# Artefato4Subtrator.net
KiCad netlist of a schematic drawn in EasyEDA
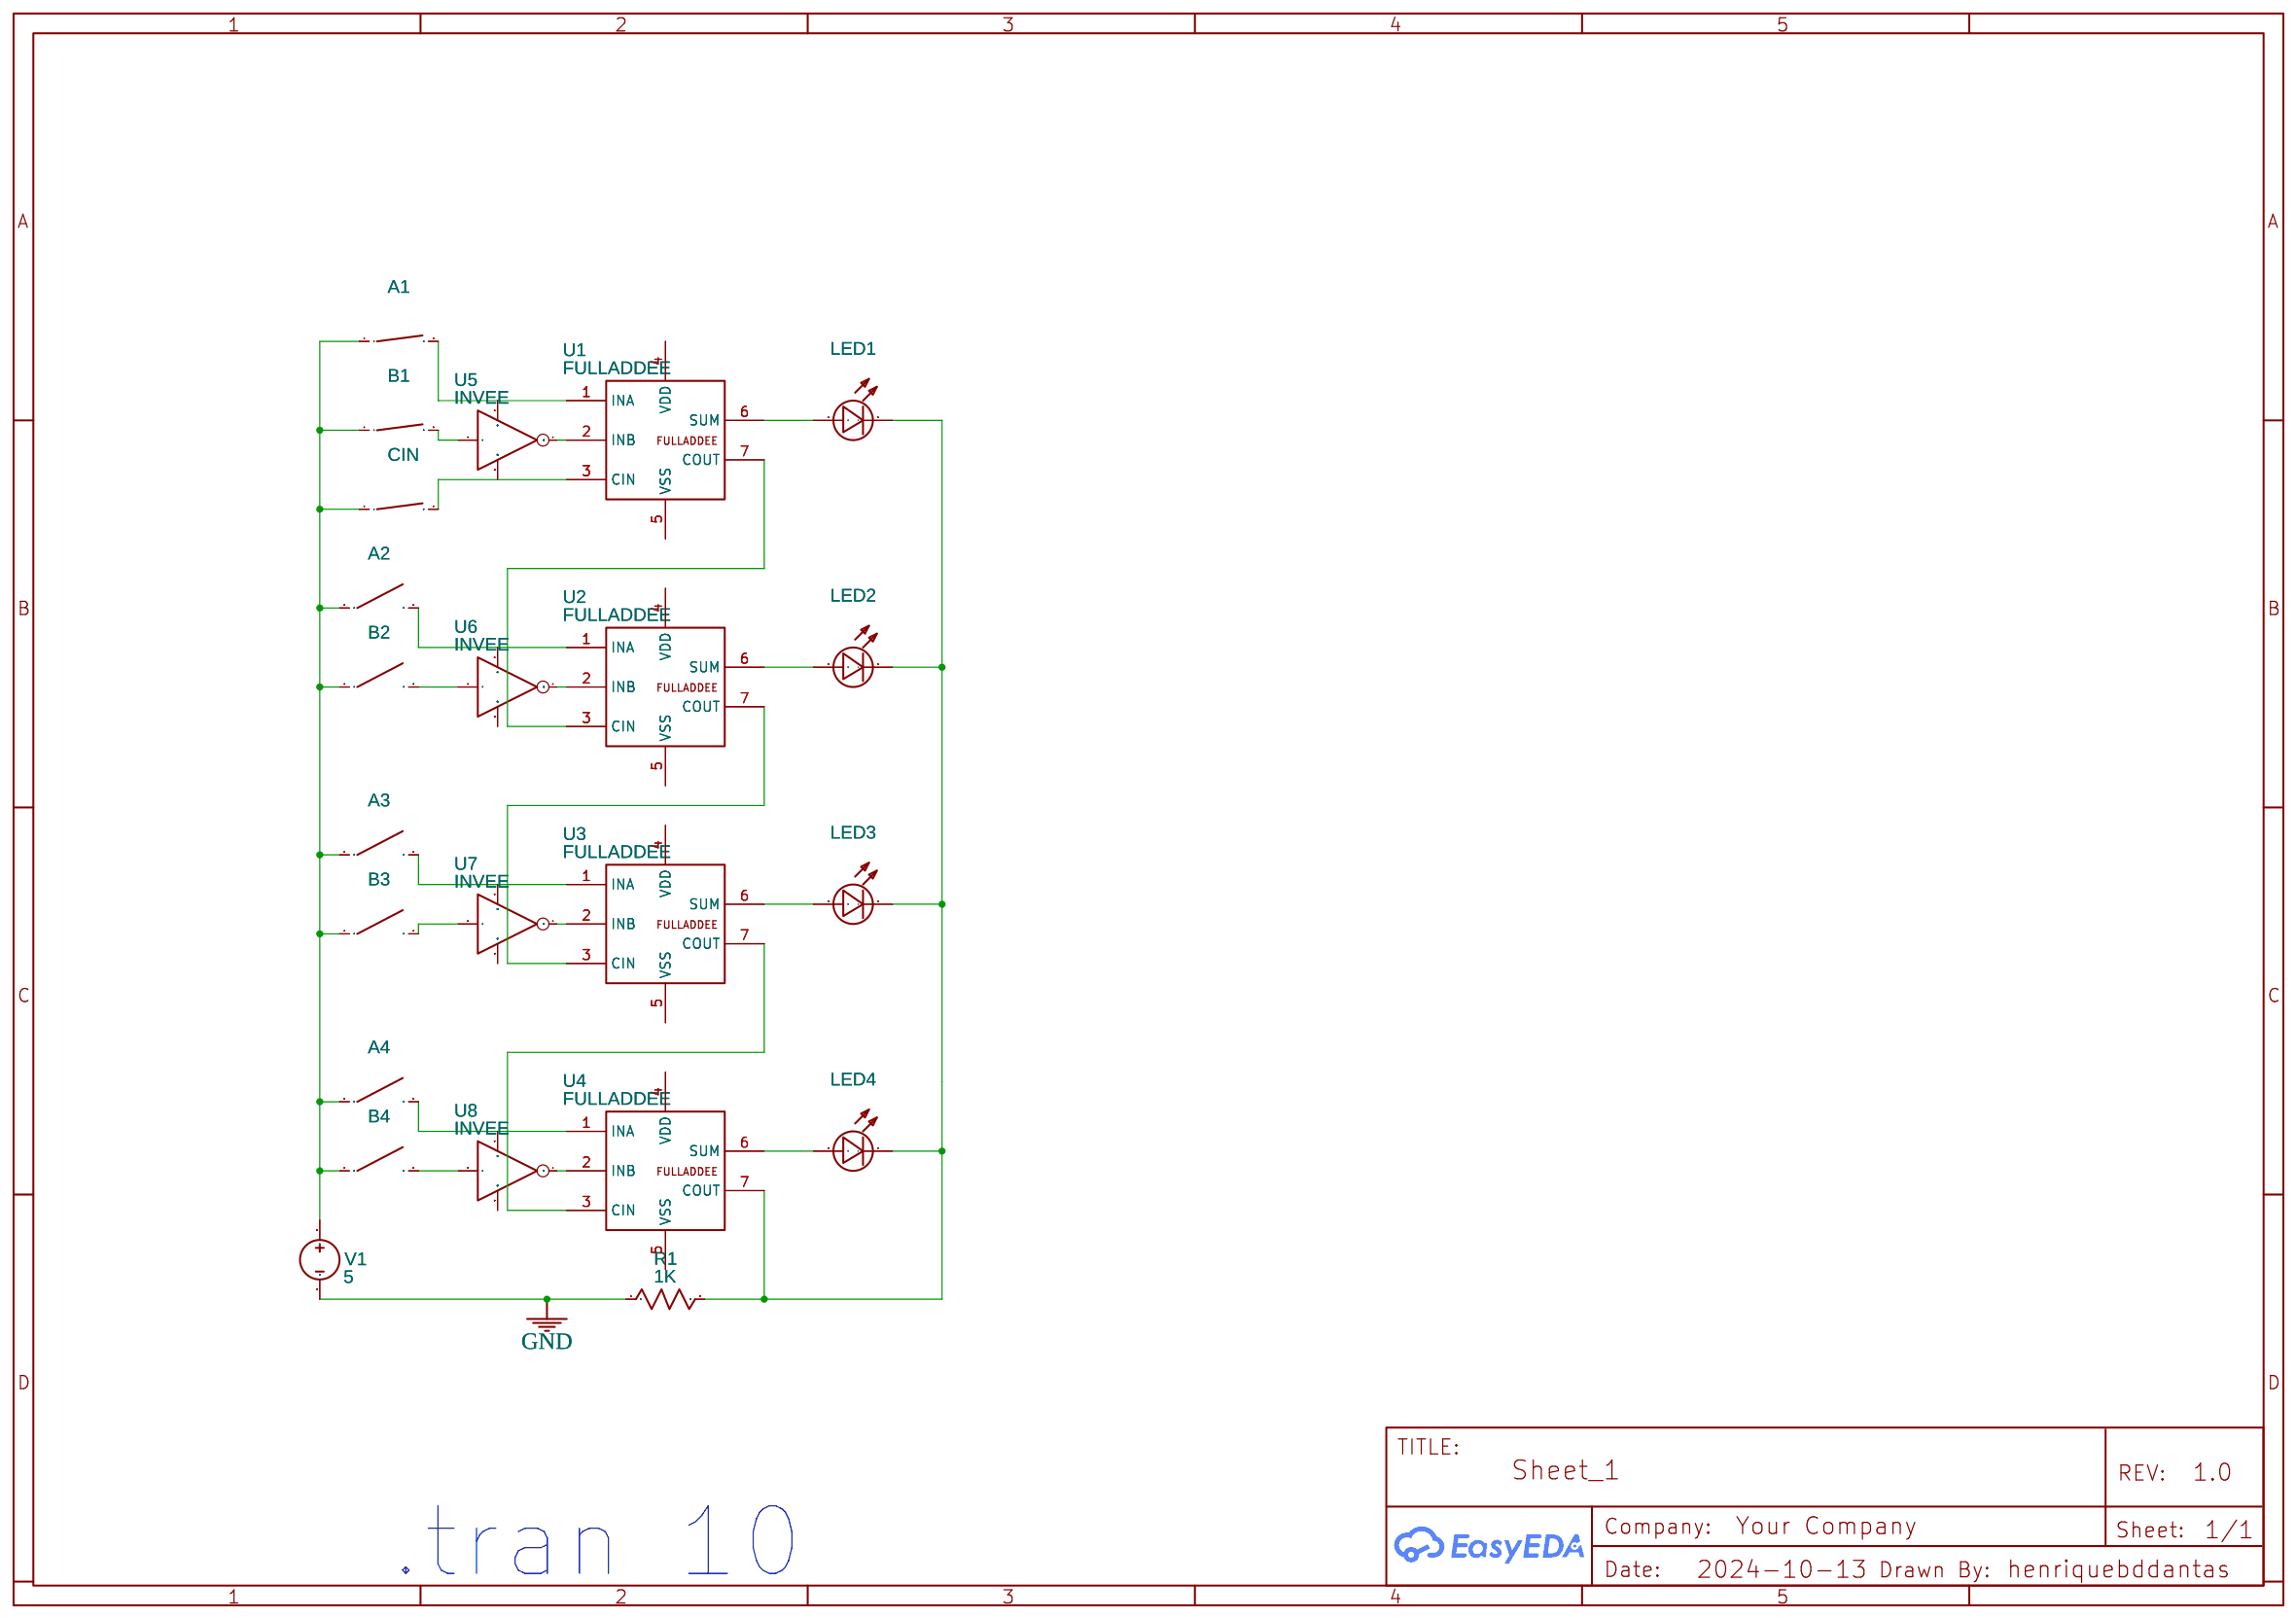
[diagram p0: schematic sheet]

(export (version "E")
  (design (tool "Eeschema 10.0.6"))
  (components
    (comp (ref "A1") (value "SPST_Open") (libsource (lib "") (part "SPST_4")))
    (comp (ref "A2") (value "SPST_Open") (libsource (lib "") (part "SPST_3")))
    (comp (ref "A3") (value "SPST_Open") (libsource (lib "") (part "SPST_3")))
    (comp (ref "A4") (value "SPST_Open") (libsource (lib "") (part "SPST_3")))
    (comp (ref "B1") (value "SPST_Open") (libsource (lib "") (part "SPST_2")))
    (comp (ref "B2") (value "SPST_Open") (libsource (lib "") (part "SPST")))
    (comp (ref "B3") (value "SPST_Open") (libsource (lib "") (part "SPST")))
    (comp (ref "B4") (value "SPST_Open") (libsource (lib "") (part "SPST")))
    (comp (ref "CIN") (value "SPST_Open") (libsource (lib "") (part "SPST_1")))
    (comp (ref "LED1") (value "LED") (libsource (lib "") (part "LED")))
    (comp (ref "LED2") (value "LED") (libsource (lib "") (part "LED")))
    (comp (ref "LED3") (value "LED") (libsource (lib "") (part "LED")))
    (comp (ref "LED4") (value "LED") (libsource (lib "") (part "LED")))
    (comp (ref "R1") (value "1K") (libsource (lib "") (part "Resistor_US")))
    (comp (ref "U1") (value "FULLADDEE") (libsource (lib "") (part "FULLADDEE")))
    (comp (ref "U2") (value "FULLADDEE") (libsource (lib "") (part "FULLADDEE")))
    (comp (ref "U3") (value "FULLADDEE") (libsource (lib "") (part "FULLADDEE")))
    (comp (ref "U4") (value "FULLADDEE") (libsource (lib "") (part "FULLADDEE")))
    (comp (ref "U5") (value "INVEE") (libsource (lib "") (part "LOGIC")))
    (comp (ref "U6") (value "INVEE") (libsource (lib "") (part "LOGIC")))
    (comp (ref "U7") (value "INVEE") (libsource (lib "") (part "LOGIC")))
    (comp (ref "U8") (value "INVEE") (libsource (lib "") (part "LOGIC")))
    (comp (ref "V1") (value "5") (libsource (lib "") (part "VDC")))
  )
  (nets
    (net (code "1") (name "GND") (class "Default")
      (node (ref "R1") (pin "1") (pinfunction "1_1") (pintype "unspecified"))
      (node (ref "V1") (pin "2") (pinfunction "2_2") (pintype "unspecified"))
    )
    (net (code "2") (name "Net-(A1-Pad1)") (class "Default")
      (node (ref "A1") (pin "1") (pinfunction "1_1") (pintype "unspecified"))
      (node (ref "A2") (pin "1") (pinfunction "1_1") (pintype "unspecified"))
      (node (ref "A3") (pin "1") (pinfunction "1_1") (pintype "unspecified"))
      (node (ref "A4") (pin "1") (pinfunction "1_1") (pintype "unspecified"))
      (node (ref "B1") (pin "1") (pinfunction "1_1") (pintype "unspecified"))
      (node (ref "B2") (pin "1") (pinfunction "1_1") (pintype "unspecified"))
      (node (ref "B3") (pin "1") (pinfunction "1_1") (pintype "unspecified"))
      (node (ref "B4") (pin "1") (pinfunction "1_1") (pintype "unspecified"))
      (node (ref "CIN") (pin "1") (pinfunction "1_1") (pintype "unspecified"))
      (node (ref "V1") (pin "1") (pinfunction "1_1") (pintype "unspecified"))
    )
    (net (code "3") (name "Net-(LED1-+)") (class "Default")
      (node (ref "LED1") (pin "1") (pinfunction "+_1") (pintype "unspecified"))
      (node (ref "U1") (pin "6") (pinfunction "SUM_6") (pintype "unspecified"))
    )
    (net (code "4") (name "Net-(LED1--)") (class "Default")
      (node (ref "LED1") (pin "2") (pinfunction "-_2") (pintype "unspecified"))
      (node (ref "LED2") (pin "2") (pinfunction "-_2") (pintype "unspecified"))
      (node (ref "LED3") (pin "2") (pinfunction "-_2") (pintype "unspecified"))
      (node (ref "LED4") (pin "2") (pinfunction "-_2") (pintype "unspecified"))
      (node (ref "R1") (pin "2") (pinfunction "2_2") (pintype "unspecified"))
      (node (ref "U4") (pin "7") (pinfunction "COUT_7") (pintype "unspecified"))
    )
    (net (code "5") (name "Net-(LED2-+)") (class "Default")
      (node (ref "LED2") (pin "1") (pinfunction "+_1") (pintype "unspecified"))
      (node (ref "U2") (pin "6") (pinfunction "SUM_6") (pintype "unspecified"))
    )
    (net (code "6") (name "Net-(LED3-+)") (class "Default")
      (node (ref "LED3") (pin "1") (pinfunction "+_1") (pintype "unspecified"))
      (node (ref "U3") (pin "6") (pinfunction "SUM_6") (pintype "unspecified"))
    )
    (net (code "7") (name "Net-(LED4-+)") (class "Default")
      (node (ref "LED4") (pin "1") (pinfunction "+_1") (pintype "unspecified"))
      (node (ref "U4") (pin "6") (pinfunction "SUM_6") (pintype "unspecified"))
    )
    (net (code "8") (name "Net-(U1-CIN)") (class "Default")
      (node (ref "CIN") (pin "2") (pinfunction "2_2") (pintype "unspecified"))
      (node (ref "U1") (pin "3") (pinfunction "CIN_3") (pintype "unspecified"))
    )
    (net (code "9") (name "Net-(U1-COUT)") (class "Default")
      (node (ref "U1") (pin "7") (pinfunction "COUT_7") (pintype "unspecified"))
      (node (ref "U2") (pin "3") (pinfunction "CIN_3") (pintype "unspecified"))
    )
    (net (code "10") (name "Net-(U1-INA)") (class "Default")
      (node (ref "A1") (pin "2") (pinfunction "2_2") (pintype "unspecified"))
      (node (ref "U1") (pin "1") (pinfunction "INA_1") (pintype "unspecified"))
    )
    (net (code "11") (name "Net-(U1-INB)") (class "Default")
      (node (ref "U1") (pin "2") (pinfunction "INB_2") (pintype "unspecified"))
      (node (ref "U5") (pin "4") (pinfunction "OUT_4") (pintype "output"))
    )
    (net (code "12") (name "Net-(U2-COUT)") (class "Default")
      (node (ref "U2") (pin "7") (pinfunction "COUT_7") (pintype "unspecified"))
      (node (ref "U3") (pin "3") (pinfunction "CIN_3") (pintype "unspecified"))
    )
    (net (code "13") (name "Net-(U2-INA)") (class "Default")
      (node (ref "A2") (pin "2") (pinfunction "2_2") (pintype "unspecified"))
      (node (ref "U2") (pin "1") (pinfunction "INA_1") (pintype "unspecified"))
    )
    (net (code "14") (name "Net-(U2-INB)") (class "Default")
      (node (ref "U2") (pin "2") (pinfunction "INB_2") (pintype "unspecified"))
      (node (ref "U6") (pin "4") (pinfunction "OUT_4") (pintype "output"))
    )
    (net (code "15") (name "Net-(U3-COUT)") (class "Default")
      (node (ref "U3") (pin "7") (pinfunction "COUT_7") (pintype "unspecified"))
      (node (ref "U4") (pin "3") (pinfunction "CIN_3") (pintype "unspecified"))
    )
    (net (code "16") (name "Net-(U3-INA)") (class "Default")
      (node (ref "A3") (pin "2") (pinfunction "2_2") (pintype "unspecified"))
      (node (ref "U3") (pin "1") (pinfunction "INA_1") (pintype "unspecified"))
    )
    (net (code "17") (name "Net-(U3-INB)") (class "Default")
      (node (ref "U3") (pin "2") (pinfunction "INB_2") (pintype "unspecified"))
      (node (ref "U7") (pin "4") (pinfunction "OUT_4") (pintype "output"))
    )
    (net (code "18") (name "Net-(U4-INA)") (class "Default")
      (node (ref "A4") (pin "2") (pinfunction "2_2") (pintype "unspecified"))
      (node (ref "U4") (pin "1") (pinfunction "INA_1") (pintype "unspecified"))
    )
    (net (code "19") (name "Net-(U4-INB)") (class "Default")
      (node (ref "U4") (pin "2") (pinfunction "INB_2") (pintype "unspecified"))
      (node (ref "U8") (pin "4") (pinfunction "OUT_4") (pintype "output"))
    )
    (net (code "20") (name "Net-(U5-IN)") (class "Default")
      (node (ref "B1") (pin "2") (pinfunction "2_2") (pintype "unspecified"))
      (node (ref "U5") (pin "1") (pinfunction "IN_1") (pintype "input"))
    )
    (net (code "21") (name "Net-(U6-IN)") (class "Default")
      (node (ref "B2") (pin "2") (pinfunction "2_2") (pintype "unspecified"))
      (node (ref "U6") (pin "1") (pinfunction "IN_1") (pintype "input"))
    )
    (net (code "22") (name "Net-(U7-IN)") (class "Default")
      (node (ref "B3") (pin "2") (pinfunction "2_2") (pintype "unspecified"))
      (node (ref "U7") (pin "1") (pinfunction "IN_1") (pintype "input"))
    )
    (net (code "23") (name "Net-(U8-IN)") (class "Default")
      (node (ref "B4") (pin "2") (pinfunction "2_2") (pintype "unspecified"))
      (node (ref "U8") (pin "1") (pinfunction "IN_1") (pintype "input"))
    )
    (net (code "24") (name "unconnected-(U1-VDD-Pad4)") (class "Default")
      (node (ref "U1") (pin "4") (pinfunction "VDD_4") (pintype "unspecified"))
    )
    (net (code "25") (name "unconnected-(U1-VSS-Pad5)") (class "Default")
      (node (ref "U1") (pin "5") (pinfunction "VSS_5") (pintype "unspecified"))
    )
    (net (code "26") (name "unconnected-(U2-VDD-Pad4)") (class "Default")
      (node (ref "U2") (pin "4") (pinfunction "VDD_4") (pintype "unspecified"))
    )
    (net (code "27") (name "unconnected-(U2-VSS-Pad5)") (class "Default")
      (node (ref "U2") (pin "5") (pinfunction "VSS_5") (pintype "unspecified"))
    )
    (net (code "28") (name "unconnected-(U3-VDD-Pad4)") (class "Default")
      (node (ref "U3") (pin "4") (pinfunction "VDD_4") (pintype "unspecified"))
    )
    (net (code "29") (name "unconnected-(U3-VSS-Pad5)") (class "Default")
      (node (ref "U3") (pin "5") (pinfunction "VSS_5") (pintype "unspecified"))
    )
    (net (code "30") (name "unconnected-(U4-VDD-Pad4)") (class "Default")
      (node (ref "U4") (pin "4") (pinfunction "VDD_4") (pintype "unspecified"))
    )
    (net (code "31") (name "unconnected-(U4-VSS-Pad5)") (class "Default")
      (node (ref "U4") (pin "5") (pinfunction "VSS_5") (pintype "unspecified"))
    )
    (net (code "32") (name "unconnected-(U5-GND-Pad3)") (class "Default")
      (node (ref "U5") (pin "3") (pinfunction "GND_3") (pintype "passive"))
    )
    (net (code "33") (name "unconnected-(U5-VDD-Pad2)") (class "Default")
      (node (ref "U5") (pin "2") (pinfunction "VDD_2") (pintype "passive"))
    )
    (net (code "34") (name "unconnected-(U6-GND-Pad3)") (class "Default")
      (node (ref "U6") (pin "3") (pinfunction "GND_3") (pintype "passive"))
    )
    (net (code "35") (name "unconnected-(U6-VDD-Pad2)") (class "Default")
      (node (ref "U6") (pin "2") (pinfunction "VDD_2") (pintype "passive"))
    )
    (net (code "36") (name "unconnected-(U7-GND-Pad3)") (class "Default")
      (node (ref "U7") (pin "3") (pinfunction "GND_3") (pintype "passive"))
    )
    (net (code "37") (name "unconnected-(U7-VDD-Pad2)") (class "Default")
      (node (ref "U7") (pin "2") (pinfunction "VDD_2") (pintype "passive"))
    )
    (net (code "38") (name "unconnected-(U8-GND-Pad3)") (class "Default")
      (node (ref "U8") (pin "3") (pinfunction "GND_3") (pintype "passive"))
    )
    (net (code "39") (name "unconnected-(U8-VDD-Pad2)") (class "Default")
      (node (ref "U8") (pin "2") (pinfunction "VDD_2") (pintype "passive"))
    )
  )
)
